# Current_sensor.net
KiCad netlist of a schematic drawn in Altium Designer
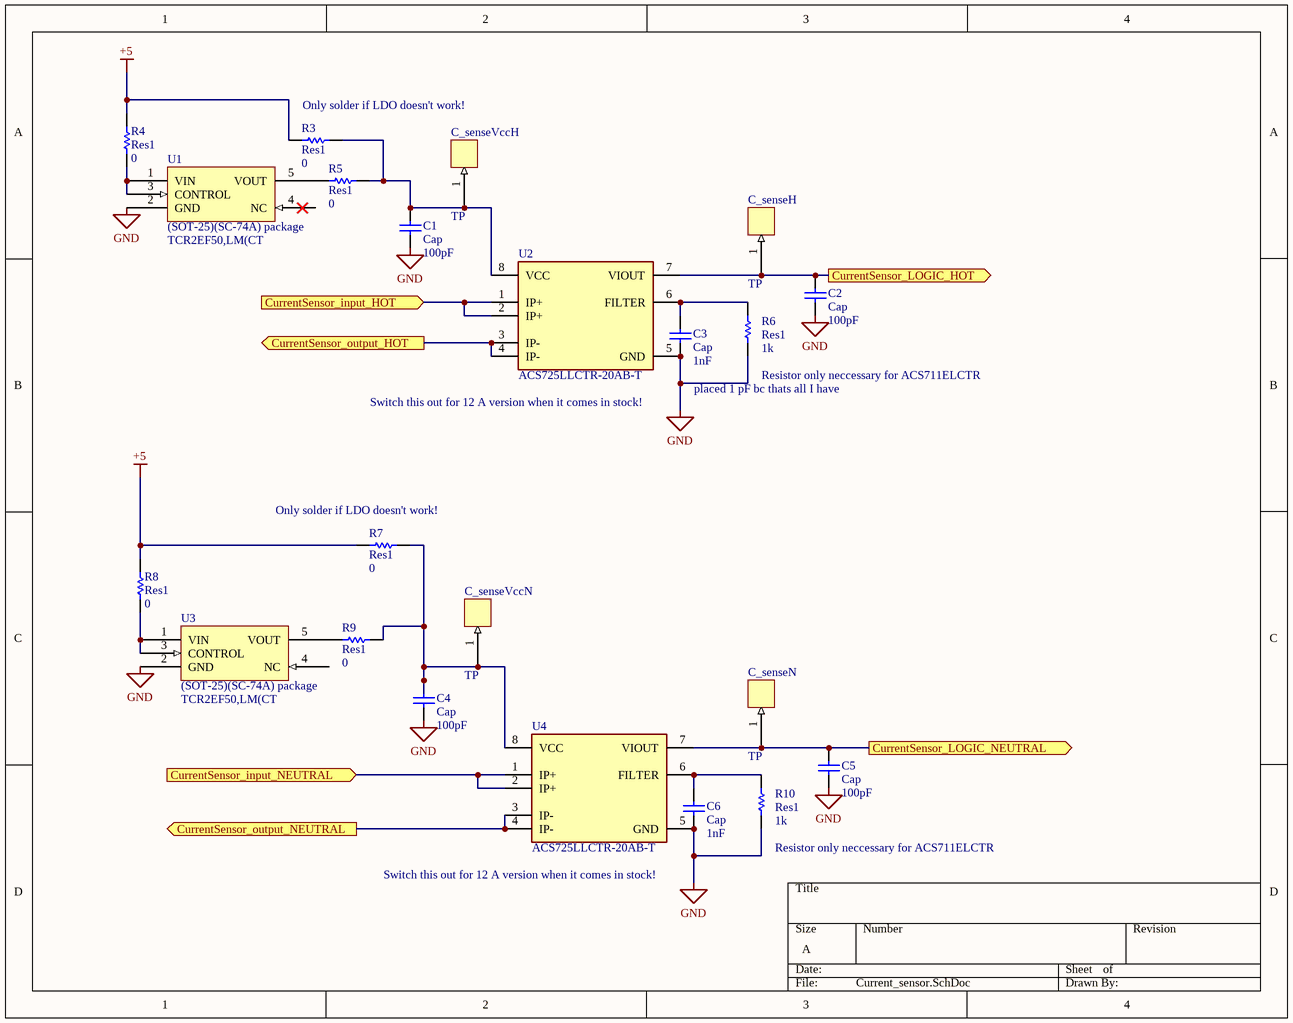
[diagram p0: Current_sensor.SchDoc]

(export (version "E")
  (design (tool "Eeschema 10.0.6"))
  (components
    (comp (ref "C1")
      (value "Cap")
      (footprint "0603")
      (description "Capacitor")
      (fields (field (name "ALTIUM_VALUE") "100pF") (field (name "PUBLISHER") "Altium Limited"))
      (libsource (lib "Miscellaneous Devices") (part "Cap"))
    )
    (comp (ref "C2")
      (value "Cap")
      (footprint "0603")
      (description "Capacitor")
      (fields (field (name "ALTIUM_VALUE") "100pF") (field (name "PUBLISHER") "Altium Limited"))
      (libsource (lib "Miscellaneous Devices") (part "Cap"))
    )
    (comp (ref "C3")
      (value "Cap")
      (footprint "0603")
      (description "Capacitor")
      (fields (field (name "ALTIUM_VALUE") "1nF") (field (name "PUBLISHER") "Altium Limited"))
      (libsource (lib "Miscellaneous Devices") (part "Cap"))
    )
    (comp (ref "C4")
      (value "Cap")
      (footprint "0603")
      (description "Capacitor")
      (fields (field (name "ALTIUM_VALUE") "100pF") (field (name "PUBLISHER") "Altium Limited"))
      (libsource (lib "Miscellaneous Devices") (part "Cap"))
    )
    (comp (ref "C5")
      (value "Cap")
      (footprint "0603")
      (description "Capacitor")
      (fields (field (name "ALTIUM_VALUE") "100pF") (field (name "PUBLISHER") "Altium Limited"))
      (libsource (lib "Miscellaneous Devices") (part "Cap"))
    )
    (comp (ref "C6")
      (value "Cap")
      (footprint "0603")
      (description "Capacitor")
      (fields (field (name "ALTIUM_VALUE") "1nF") (field (name "PUBLISHER") "Altium Limited"))
      (libsource (lib "Miscellaneous Devices") (part "Cap"))
    )
    (comp (ref "C_senseH") (value "TP") (footprint "TP") (libsource (lib "TestPoint") (part "TP")))
    (comp (ref "C_senseN") (value "TP") (footprint "TP") (libsource (lib "TestPoint") (part "TP")))
    (comp (ref "C_senseVccH") (value "TP") (footprint "TP") (libsource (lib "TestPoint") (part "TP")))
    (comp (ref "C_senseVccN") (value "TP") (footprint "TP") (libsource (lib "TestPoint") (part "TP")))
    (comp (ref "R3")
      (value "Res1")
      (footprint "0603")
      (description "Resistor")
      (fields (field (name "ALTIUM_VALUE") "0") (field (name "PUBLISHER") "Altium Limited"))
      (libsource (lib "Miscellaneous Devices") (part "Res1"))
    )
    (comp (ref "R4")
      (value "Res1")
      (footprint "0603")
      (description "Resistor")
      (fields (field (name "ALTIUM_VALUE") "0") (field (name "PUBLISHER") "Altium Limited"))
      (libsource (lib "Miscellaneous Devices") (part "Res1"))
    )
    (comp (ref "R5")
      (value "Res1")
      (footprint "0603")
      (description "Resistor")
      (fields (field (name "ALTIUM_VALUE") "0") (field (name "PUBLISHER") "Altium Limited"))
      (libsource (lib "Miscellaneous Devices") (part "Res1"))
    )
    (comp (ref "R6")
      (value "Res1")
      (footprint "0603")
      (description "Resistor")
      (fields (field (name "ALTIUM_VALUE") "1k") (field (name "PUBLISHER") "Altium Limited"))
      (libsource (lib "Miscellaneous Devices") (part "Res1"))
    )
    (comp (ref "R7")
      (value "Res1")
      (footprint "0603")
      (description "Resistor")
      (fields (field (name "ALTIUM_VALUE") "0") (field (name "PUBLISHER") "Altium Limited"))
      (libsource (lib "Miscellaneous Devices") (part "Res1"))
    )
    (comp (ref "R8")
      (value "Res1")
      (footprint "0603")
      (description "Resistor")
      (fields (field (name "ALTIUM_VALUE") "0") (field (name "PUBLISHER") "Altium Limited"))
      (libsource (lib "Miscellaneous Devices") (part "Res1"))
    )
    (comp (ref "R9")
      (value "Res1")
      (footprint "0603")
      (description "Resistor")
      (fields (field (name "ALTIUM_VALUE") "0") (field (name "PUBLISHER") "Altium Limited"))
      (libsource (lib "Miscellaneous Devices") (part "Res1"))
    )
    (comp (ref "R10")
      (value "Res1")
      (footprint "0603")
      (description "Resistor")
      (fields (field (name "ALTIUM_VALUE") "1k") (field (name "PUBLISHER") "Altium Limited"))
      (libsource (lib "Miscellaneous Devices") (part "Res1"))
    )
    (comp (ref "U1")
      (value "TCR2EF50,LM(CT")
      (footprint "SOT95P275X130-5N")
      (libsource (lib "TCR2EF50,LM(CT") (part "TCR2EF50,LM(CT"))
    )
    (comp (ref "U2")
      (value "ACS725LLCTR-20AB-T")
      (footprint "FP-LCN-8-IPC_B")
      (description "SENSOR CURRENT HALL 20A AC/DC")
      (libsource (lib "Altium Content Vault") (part "24c2fda9b8a0b4b902445efe0d7face"))
    )
    (comp (ref "U3")
      (value "TCR2EF50,LM(CT")
      (footprint "SOT95P275X130-5N")
      (libsource (lib "TCR2EF50,LM(CT") (part "TCR2EF50,LM(CT"))
    )
    (comp (ref "U4")
      (value "ACS725LLCTR-20AB-T")
      (footprint "FP-LCN-8-IPC_B")
      (description "SENSOR CURRENT HALL 20A AC/DC")
      (libsource (lib "Altium Content Vault") (part "24c2fda9b8a0b4b902445efe0d7face"))
    )
  )
  (nets
    (net (code "1") (name "+5") (class "Default")
      (node (ref "R3") (pin "2") (pinfunction "2_2") (pintype "passive"))
      (node (ref "R4") (pin "1") (pinfunction "1_1") (pintype "passive"))
      (node (ref "R7") (pin "2") (pinfunction "2_2") (pintype "passive"))
      (node (ref "R8") (pin "1") (pinfunction "1_1") (pintype "passive"))
    )
    (net (code "2") (name "/CurrentSensor_LOGIC_HOT") (class "Default")
      (node (ref "C2") (pin "2") (pinfunction "2_2") (pintype "passive"))
      (node (ref "C_senseH") (pin "1") (pintype "input"))
      (node (ref "U2") (pin "7") (pinfunction "VIOUT_7") (pintype "passive"))
    )
    (net (code "3") (name "/CurrentSensor_LOGIC_NEUTRAL") (class "Default")
      (node (ref "C5") (pin "2") (pinfunction "2_2") (pintype "passive"))
      (node (ref "C_senseN") (pin "1") (pintype "input"))
      (node (ref "U4") (pin "7") (pinfunction "VIOUT_7") (pintype "passive"))
    )
    (net (code "4") (name "/CurrentSensor_input_HOT") (class "Default")
      (node (ref "U2") (pin "1") (pinfunction "IP+_1") (pintype "passive"))
      (node (ref "U2") (pin "2") (pinfunction "IP+_2") (pintype "passive"))
    )
    (net (code "5") (name "/CurrentSensor_input_NEUTRAL") (class "Default")
      (node (ref "U4") (pin "1") (pinfunction "IP+_1") (pintype "passive"))
      (node (ref "U4") (pin "2") (pinfunction "IP+_2") (pintype "passive"))
    )
    (net (code "6") (name "/CurrentSensor_output_HOT") (class "Default")
      (node (ref "U2") (pin "3") (pinfunction "IP-_3") (pintype "passive"))
      (node (ref "U2") (pin "4") (pinfunction "IP-_4") (pintype "passive"))
    )
    (net (code "7") (name "/CurrentSensor_output_NEUTRAL") (class "Default")
      (node (ref "U4") (pin "3") (pinfunction "IP-_3") (pintype "passive"))
      (node (ref "U4") (pin "4") (pinfunction "IP-_4") (pintype "passive"))
    )
    (net (code "8") (name "GND") (class "Default")
      (node (ref "C1") (pin "1") (pinfunction "1_1") (pintype "passive"))
      (node (ref "C2") (pin "1") (pinfunction "1_1") (pintype "passive"))
      (node (ref "C3") (pin "1") (pinfunction "1_1") (pintype "passive"))
      (node (ref "C4") (pin "1") (pinfunction "1_1") (pintype "passive"))
      (node (ref "C5") (pin "1") (pinfunction "1_1") (pintype "passive"))
      (node (ref "C6") (pin "1") (pinfunction "1_1") (pintype "passive"))
      (node (ref "R10") (pin "1") (pinfunction "1_1") (pintype "passive"))
      (node (ref "R6") (pin "1") (pinfunction "1_1") (pintype "passive"))
      (node (ref "U1") (pin "2") (pinfunction "GND_2") (pintype "power_in"))
      (node (ref "U2") (pin "5") (pinfunction "GND_5") (pintype "power_in"))
      (node (ref "U3") (pin "2") (pinfunction "GND_2") (pintype "power_in"))
      (node (ref "U4") (pin "5") (pinfunction "GND_5") (pintype "power_in"))
    )
    (net (code "9") (name "Net-(U1-CONTROL)") (class "Default")
      (node (ref "R4") (pin "2") (pinfunction "2_2") (pintype "passive"))
      (node (ref "U1") (pin "1") (pinfunction "VIN_1") (pintype "power_in"))
      (node (ref "U1") (pin "3") (pinfunction "CONTROL_3") (pintype "input"))
    )
    (net (code "10") (name "Net-(U1-VOUT)") (class "Default")
      (node (ref "R5") (pin "2") (pinfunction "2_2") (pintype "passive"))
      (node (ref "U1") (pin "5") (pinfunction "VOUT_5") (pintype "power_in"))
    )
    (net (code "11") (name "Net-(U2-FILTER)") (class "Default")
      (node (ref "C3") (pin "2") (pinfunction "2_2") (pintype "passive"))
      (node (ref "R6") (pin "2") (pinfunction "2_2") (pintype "passive"))
      (node (ref "U2") (pin "6") (pinfunction "FILTER_6") (pintype "passive"))
    )
    (net (code "12") (name "Net-(U2-VCC)") (class "Default")
      (node (ref "C1") (pin "2") (pinfunction "2_2") (pintype "passive"))
      (node (ref "C_senseVccH") (pin "1") (pintype "input"))
      (node (ref "R3") (pin "1") (pinfunction "1_1") (pintype "passive"))
      (node (ref "R5") (pin "1") (pinfunction "1_1") (pintype "passive"))
      (node (ref "U2") (pin "8") (pinfunction "VCC_8") (pintype "power_in"))
    )
    (net (code "13") (name "Net-(U3-CONTROL)") (class "Default")
      (node (ref "R8") (pin "2") (pinfunction "2_2") (pintype "passive"))
      (node (ref "U3") (pin "1") (pinfunction "VIN_1") (pintype "power_in"))
      (node (ref "U3") (pin "3") (pinfunction "CONTROL_3") (pintype "input"))
    )
    (net (code "14") (name "Net-(U3-VOUT)") (class "Default")
      (node (ref "R9") (pin "2") (pinfunction "2_2") (pintype "passive"))
      (node (ref "U3") (pin "5") (pinfunction "VOUT_5") (pintype "power_in"))
    )
    (net (code "15") (name "Net-(U4-FILTER)") (class "Default")
      (node (ref "C6") (pin "2") (pinfunction "2_2") (pintype "passive"))
      (node (ref "R10") (pin "2") (pinfunction "2_2") (pintype "passive"))
      (node (ref "U4") (pin "6") (pinfunction "FILTER_6") (pintype "passive"))
    )
    (net (code "16") (name "Net-(U4-VCC)") (class "Default")
      (node (ref "C4") (pin "2") (pinfunction "2_2") (pintype "passive"))
      (node (ref "C_senseVccN") (pin "1") (pintype "input"))
      (node (ref "R7") (pin "1") (pinfunction "1_1") (pintype "passive"))
      (node (ref "R9") (pin "1") (pinfunction "1_1") (pintype "passive"))
      (node (ref "U4") (pin "8") (pinfunction "VCC_8") (pintype "power_in"))
    )
    (net (code "17") (name "unconnected-(U1-NC-Pad4)") (class "Default")
      (node (ref "U1") (pin "4") (pinfunction "NC_4") (pintype "input"))
    )
    (net (code "18") (name "unconnected-(U3-NC-Pad4)") (class "Default")
      (node (ref "U3") (pin "4") (pinfunction "NC_4") (pintype "input"))
    )
  )
)
